# 4_64.net
KiCad netlist of a schematic drawn in EasyEDA
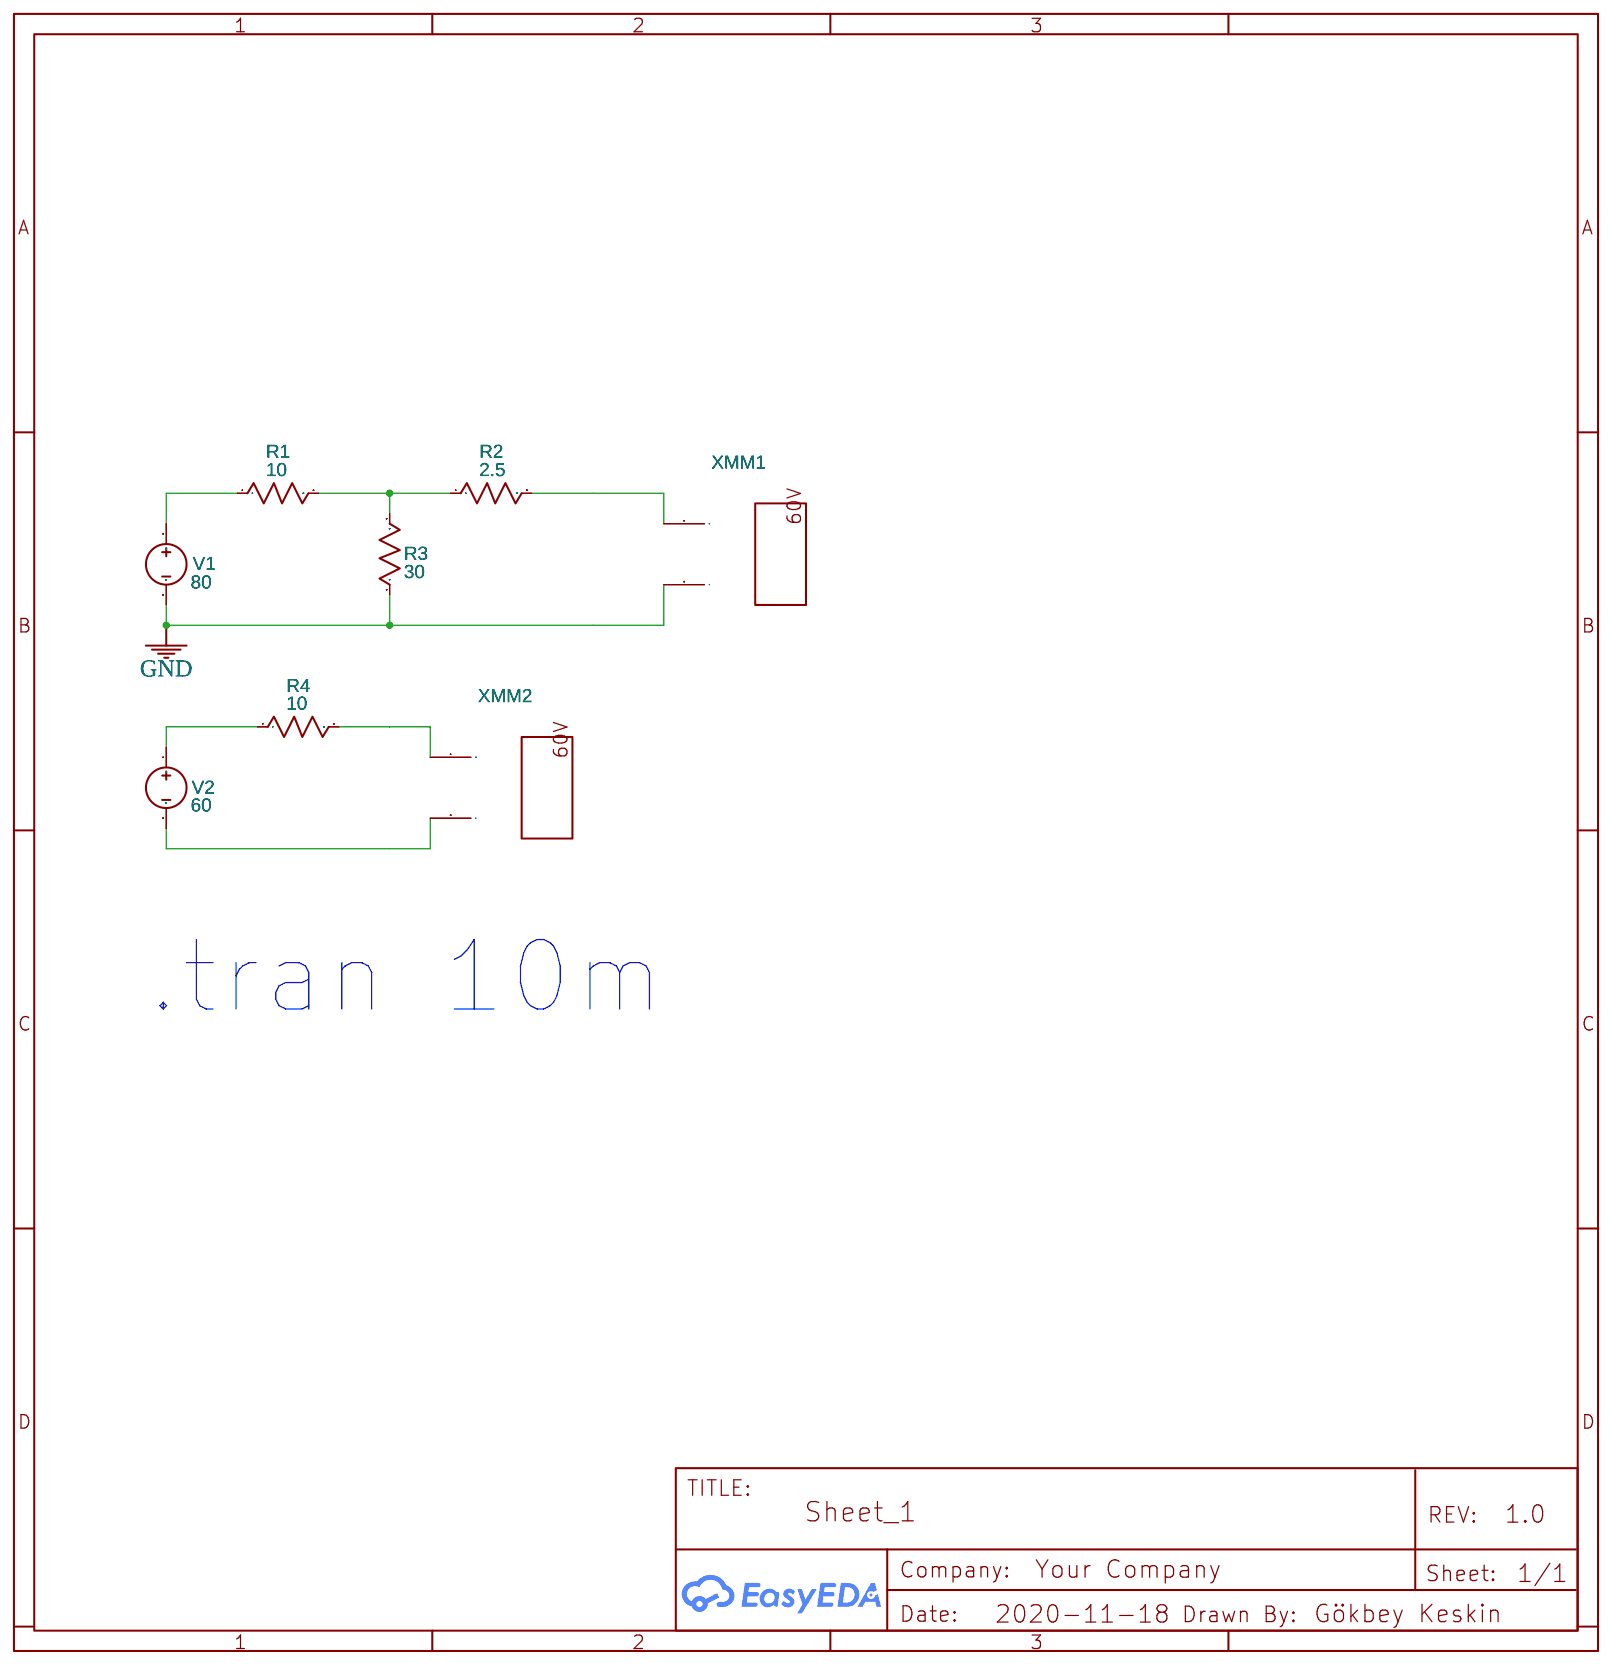
[diagram p0: schematic sheet]

(export (version "E")
  (design (tool "Eeschema 10.0.6"))
  (components
    (comp (ref "R1") (value "10") (libsource (lib "") (part "Resistor_US")))
    (comp (ref "R2") (value "2.5") (libsource (lib "") (part "Resistor_US")))
    (comp (ref "R3") (value "30") (libsource (lib "") (part "Resistor_US_1")))
    (comp (ref "R4") (value "10") (libsource (lib "") (part "Resistor_US")))
    (comp (ref "V1") (value "80") (libsource (lib "") (part "VDC")))
    (comp (ref "V2") (value "60") (libsource (lib "") (part "VDC")))
    (comp (ref "XMM1") (value "Multimeter") (libsource (lib "") (part "MULTIMETER")))
    (comp (ref "XMM2") (value "Multimeter") (libsource (lib "") (part "MULTIMETER")))
  )
  (nets
    (net (code "1") (name "GND") (class "Default")
      (node (ref "R3") (pin "1") (pinfunction "1_1") (pintype "unspecified"))
      (node (ref "V1") (pin "2") (pinfunction "2_2") (pintype "unspecified"))
      (node (ref "XMM1") (pin "2") (pinfunction "I_2") (pintype "unspecified"))
    )
    (net (code "2") (name "Net-(R1-Pad1)") (class "Default")
      (node (ref "R1") (pin "1") (pinfunction "1_1") (pintype "unspecified"))
      (node (ref "V1") (pin "1") (pinfunction "1_1") (pintype "unspecified"))
    )
    (net (code "3") (name "Net-(R1-Pad2)") (class "Default")
      (node (ref "R1") (pin "2") (pinfunction "2_2") (pintype "unspecified"))
      (node (ref "R2") (pin "1") (pinfunction "1_1") (pintype "unspecified"))
      (node (ref "R3") (pin "2") (pinfunction "2_2") (pintype "unspecified"))
    )
    (net (code "4") (name "Net-(R4-Pad1)") (class "Default")
      (node (ref "R4") (pin "1") (pinfunction "1_1") (pintype "unspecified"))
      (node (ref "V2") (pin "1") (pinfunction "1_1") (pintype "unspecified"))
    )
    (net (code "5") (name "Net-(XMM1-+)") (class "Default")
      (node (ref "R2") (pin "2") (pinfunction "2_2") (pintype "unspecified"))
      (node (ref "XMM1") (pin "1") (pinfunction "+_1") (pintype "unspecified"))
    )
    (net (code "6") (name "Net-(XMM2-+)") (class "Default")
      (node (ref "R4") (pin "2") (pinfunction "2_2") (pintype "unspecified"))
      (node (ref "XMM2") (pin "1") (pinfunction "+_1") (pintype "unspecified"))
    )
    (net (code "7") (name "Net-(XMM2-I)") (class "Default")
      (node (ref "V2") (pin "2") (pinfunction "2_2") (pintype "unspecified"))
      (node (ref "XMM2") (pin "2") (pinfunction "I_2") (pintype "unspecified"))
    )
  )
)
